# 4313_Breakout_V2.net
KiCad netlist of a schematic drawn in EAGLE
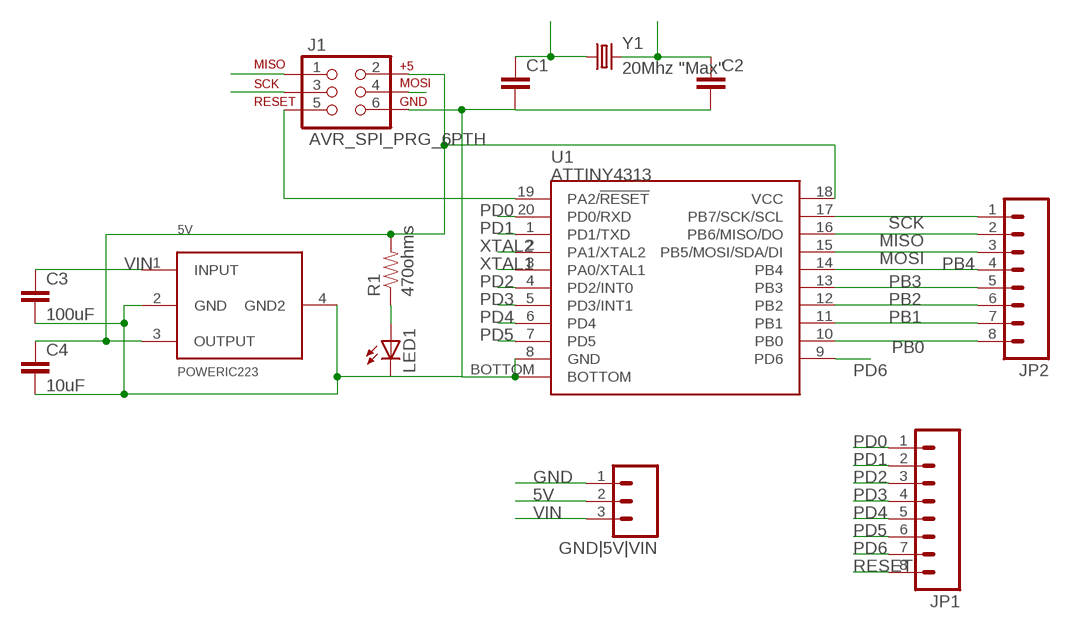
[diagram p0: schematic, sheet 1]

(export (version "E")
  (design (tool "Eeschema 10.0.6"))
  (components
    (comp (ref "5V")
      (value "POWERIC223")
      (footprint "eagle-import:SOT223")
      (libsource (lib "eagle-import") (part "POWERIC223"))
    )
    (comp (ref "C1")
      (value "CAP1206")
      (footprint "eagle-import:1206")
      (libsource (lib "eagle-import") (part "SparkFun-Passives_CAP1206"))
    )
    (comp (ref "C2")
      (value "CAP1206")
      (footprint "eagle-import:1206")
      (libsource (lib "eagle-import") (part "SparkFun-Passives_CAP1206"))
    )
    (comp (ref "C3")
      (value "100uF")
      (footprint "eagle-import:1210")
      (libsource (lib "eagle-import") (part "CAP1210"))
    )
    (comp (ref "C4")
      (value "10uF")
      (footprint "eagle-import:1210")
      (libsource (lib "eagle-import") (part "CAP1210"))
    )
    (comp (ref "GND|5V|VIN")
      (value "M03PTH")
      (footprint "eagle-import:1X03")
      (libsource (lib "eagle-import") (part "M03PTH"))
    )
    (comp (ref "J1")
      (value "AVR_SPI_PRG_6PTH")
      (footprint "eagle-import:2X3")
      (libsource (lib "eagle-import") (part "AVR_SPI_PRG_6PTH"))
    )
    (comp (ref "JP1")
      (value "M081X08")
      (footprint "eagle-import:1X08")
      (libsource (lib "eagle-import") (part "M081X08"))
    )
    (comp (ref "JP2")
      (value "M081X08")
      (footprint "eagle-import:1X08")
      (libsource (lib "eagle-import") (part "M081X08"))
    )
    (comp (ref "LED1")
      (value "LED1206")
      (footprint "eagle-import:LED-1206")
      (libsource (lib "eagle-import") (part "LED1206"))
    )
    (comp (ref "R1")
      (value "470ohms")
      (footprint "eagle-import:1206")
      (libsource (lib "eagle-import") (part "RESISTOR1206"))
    )
    (comp (ref "U1")
      (value "ATTINY4313")
      (footprint "eagle-import:MLF-20")
      (libsource (lib "eagle-import") (part "ATTINY4313"))
    )
    (comp (ref "Y1")
      (value "20Mhz \"Max\"")
      (footprint "eagle-import:CRYSTAL-SMD-5X3")
      (libsource (lib "eagle-import") (part "CRYSTAL5X3"))
    )
  )
  (nets
    (net (code "1") (name "/5V") (class "Default")
      (node (ref "5V") (pin "3") (pinfunction "OUTPUT_3") (pintype "bidirectional"))
      (node (ref "C4") (pin "1") (pinfunction "1_1") (pintype "passive"))
      (node (ref "GND|5V|VIN") (pin "2") (pinfunction "2_2") (pintype "passive"))
      (node (ref "J1") (pin "2") (pinfunction "2_2") (pintype "passive"))
      (node (ref "R1") (pin "2") (pinfunction "2_2") (pintype "passive"))
      (node (ref "U1") (pin "18") (pinfunction "VCC_18") (pintype "bidirectional"))
    )
    (net (code "2") (name "/GND") (class "Default")
      (node (ref "5V") (pin "2") (pinfunction "GND_2") (pintype "bidirectional"))
      (node (ref "5V") (pin "4") (pinfunction "GND2_4") (pintype "bidirectional"))
      (node (ref "C1") (pin "2") (pinfunction "2_2") (pintype "passive"))
      (node (ref "C2") (pin "2") (pinfunction "2_2") (pintype "passive"))
      (node (ref "C3") (pin "2") (pinfunction "2_2") (pintype "passive"))
      (node (ref "C4") (pin "2") (pinfunction "2_2") (pintype "passive"))
      (node (ref "GND|5V|VIN") (pin "1") (pinfunction "1_1") (pintype "passive"))
      (node (ref "J1") (pin "6") (pinfunction "6_6") (pintype "passive"))
      (node (ref "LED1") (pin "C") (pinfunction "C_C") (pintype "passive"))
      (node (ref "U1") (pin "8") (pinfunction "GND_8") (pintype "bidirectional"))
      (node (ref "U1") (pin "BOTTOM") (pinfunction "BOTTOM_BOTTOM") (pintype "bidirectional"))
    )
    (net (code "3") (name "/MISO") (class "Default")
      (node (ref "J1") (pin "1") (pinfunction "1_1") (pintype "passive"))
      (node (ref "JP2") (pin "2") (pinfunction "2_2") (pintype "passive"))
      (node (ref "U1") (pin "16") (pinfunction "PB6/MISO/DO_16") (pintype "bidirectional"))
    )
    (net (code "4") (name "/MOSI") (class "Default")
      (node (ref "J1") (pin "4") (pinfunction "4_4") (pintype "passive"))
      (node (ref "JP2") (pin "3") (pinfunction "3_3") (pintype "passive"))
      (node (ref "U1") (pin "15") (pinfunction "PB5/MOSI/SDA/DI_15") (pintype "bidirectional"))
    )
    (net (code "5") (name "/PB0") (class "Default")
      (node (ref "JP2") (pin "8") (pinfunction "8_8") (pintype "passive"))
      (node (ref "U1") (pin "10") (pinfunction "PB0_10") (pintype "bidirectional"))
    )
    (net (code "6") (name "/PB1") (class "Default")
      (node (ref "JP2") (pin "7") (pinfunction "7_7") (pintype "passive"))
      (node (ref "U1") (pin "11") (pinfunction "PB1_11") (pintype "bidirectional"))
    )
    (net (code "7") (name "/PB2") (class "Default")
      (node (ref "JP2") (pin "6") (pinfunction "6_6") (pintype "passive"))
      (node (ref "U1") (pin "12") (pinfunction "PB2_12") (pintype "bidirectional"))
    )
    (net (code "8") (name "/PB3") (class "Default")
      (node (ref "JP2") (pin "5") (pinfunction "5_5") (pintype "passive"))
      (node (ref "U1") (pin "13") (pinfunction "PB3_13") (pintype "bidirectional"))
    )
    (net (code "9") (name "/PB4") (class "Default")
      (node (ref "JP2") (pin "4") (pinfunction "4_4") (pintype "passive"))
      (node (ref "U1") (pin "14") (pinfunction "PB4_14") (pintype "bidirectional"))
    )
    (net (code "10") (name "/PD0") (class "Default")
      (node (ref "JP1") (pin "1") (pinfunction "1_1") (pintype "passive"))
      (node (ref "U1") (pin "20") (pinfunction "PD0/RXD_20") (pintype "bidirectional"))
    )
    (net (code "11") (name "/PD1") (class "Default")
      (node (ref "JP1") (pin "2") (pinfunction "2_2") (pintype "passive"))
      (node (ref "U1") (pin "1") (pinfunction "PD1/TXD_1") (pintype "bidirectional"))
    )
    (net (code "12") (name "/PD2") (class "Default")
      (node (ref "JP1") (pin "3") (pinfunction "3_3") (pintype "passive"))
      (node (ref "U1") (pin "4") (pinfunction "PD2/INT0_4") (pintype "bidirectional"))
    )
    (net (code "13") (name "/PD3") (class "Default")
      (node (ref "JP1") (pin "4") (pinfunction "4_4") (pintype "passive"))
      (node (ref "U1") (pin "5") (pinfunction "PD3/INT1_5") (pintype "bidirectional"))
    )
    (net (code "14") (name "/PD4") (class "Default")
      (node (ref "JP1") (pin "5") (pinfunction "5_5") (pintype "passive"))
      (node (ref "U1") (pin "6") (pinfunction "PD4_6") (pintype "bidirectional"))
    )
    (net (code "15") (name "/PD5") (class "Default")
      (node (ref "JP1") (pin "6") (pinfunction "6_6") (pintype "passive"))
      (node (ref "U1") (pin "7") (pinfunction "PD5_7") (pintype "bidirectional"))
    )
    (net (code "16") (name "/PD6") (class "Default")
      (node (ref "JP1") (pin "7") (pinfunction "7_7") (pintype "passive"))
      (node (ref "U1") (pin "9") (pinfunction "PD6_9") (pintype "bidirectional"))
    )
    (net (code "17") (name "/RESET") (class "Default")
      (node (ref "J1") (pin "5") (pinfunction "5_5") (pintype "passive"))
      (node (ref "JP1") (pin "8") (pinfunction "8_8") (pintype "passive"))
      (node (ref "U1") (pin "19") (pinfunction "PA2/~{RESET}_19") (pintype "bidirectional"))
    )
    (net (code "18") (name "/SCK") (class "Default")
      (node (ref "J1") (pin "3") (pinfunction "3_3") (pintype "passive"))
      (node (ref "JP2") (pin "1") (pinfunction "1_1") (pintype "passive"))
      (node (ref "U1") (pin "17") (pinfunction "PB7/SCK/SCL_17") (pintype "bidirectional"))
    )
    (net (code "19") (name "/VIN") (class "Default")
      (node (ref "5V") (pin "1") (pinfunction "INPUT_1") (pintype "bidirectional"))
      (node (ref "C3") (pin "1") (pinfunction "1_1") (pintype "passive"))
      (node (ref "GND|5V|VIN") (pin "3") (pinfunction "3_3") (pintype "passive"))
    )
    (net (code "20") (name "/XTAL1") (class "Default")
      (node (ref "C1") (pin "1") (pinfunction "1_1") (pintype "passive"))
      (node (ref "U1") (pin "3") (pinfunction "PA0/XTAL1_3") (pintype "bidirectional"))
      (node (ref "Y1") (pin "1") (pinfunction "1_1") (pintype "passive"))
    )
    (net (code "21") (name "/XTAL2") (class "Default")
      (node (ref "C2") (pin "1") (pinfunction "1_1") (pintype "passive"))
      (node (ref "U1") (pin "2") (pinfunction "PA1/XTAL2_2") (pintype "bidirectional"))
      (node (ref "Y1") (pin "3") (pinfunction "2_3") (pintype "passive"))
    )
    (net (code "22") (name "Net-(LED1-PadA)") (class "Default")
      (node (ref "LED1") (pin "A") (pinfunction "A_A") (pintype "passive"))
      (node (ref "R1") (pin "1") (pinfunction "1_1") (pintype "passive"))
    )
  )
)
